# OSSI-1_EPS.net
KiCad netlist of a schematic drawn in EAGLE
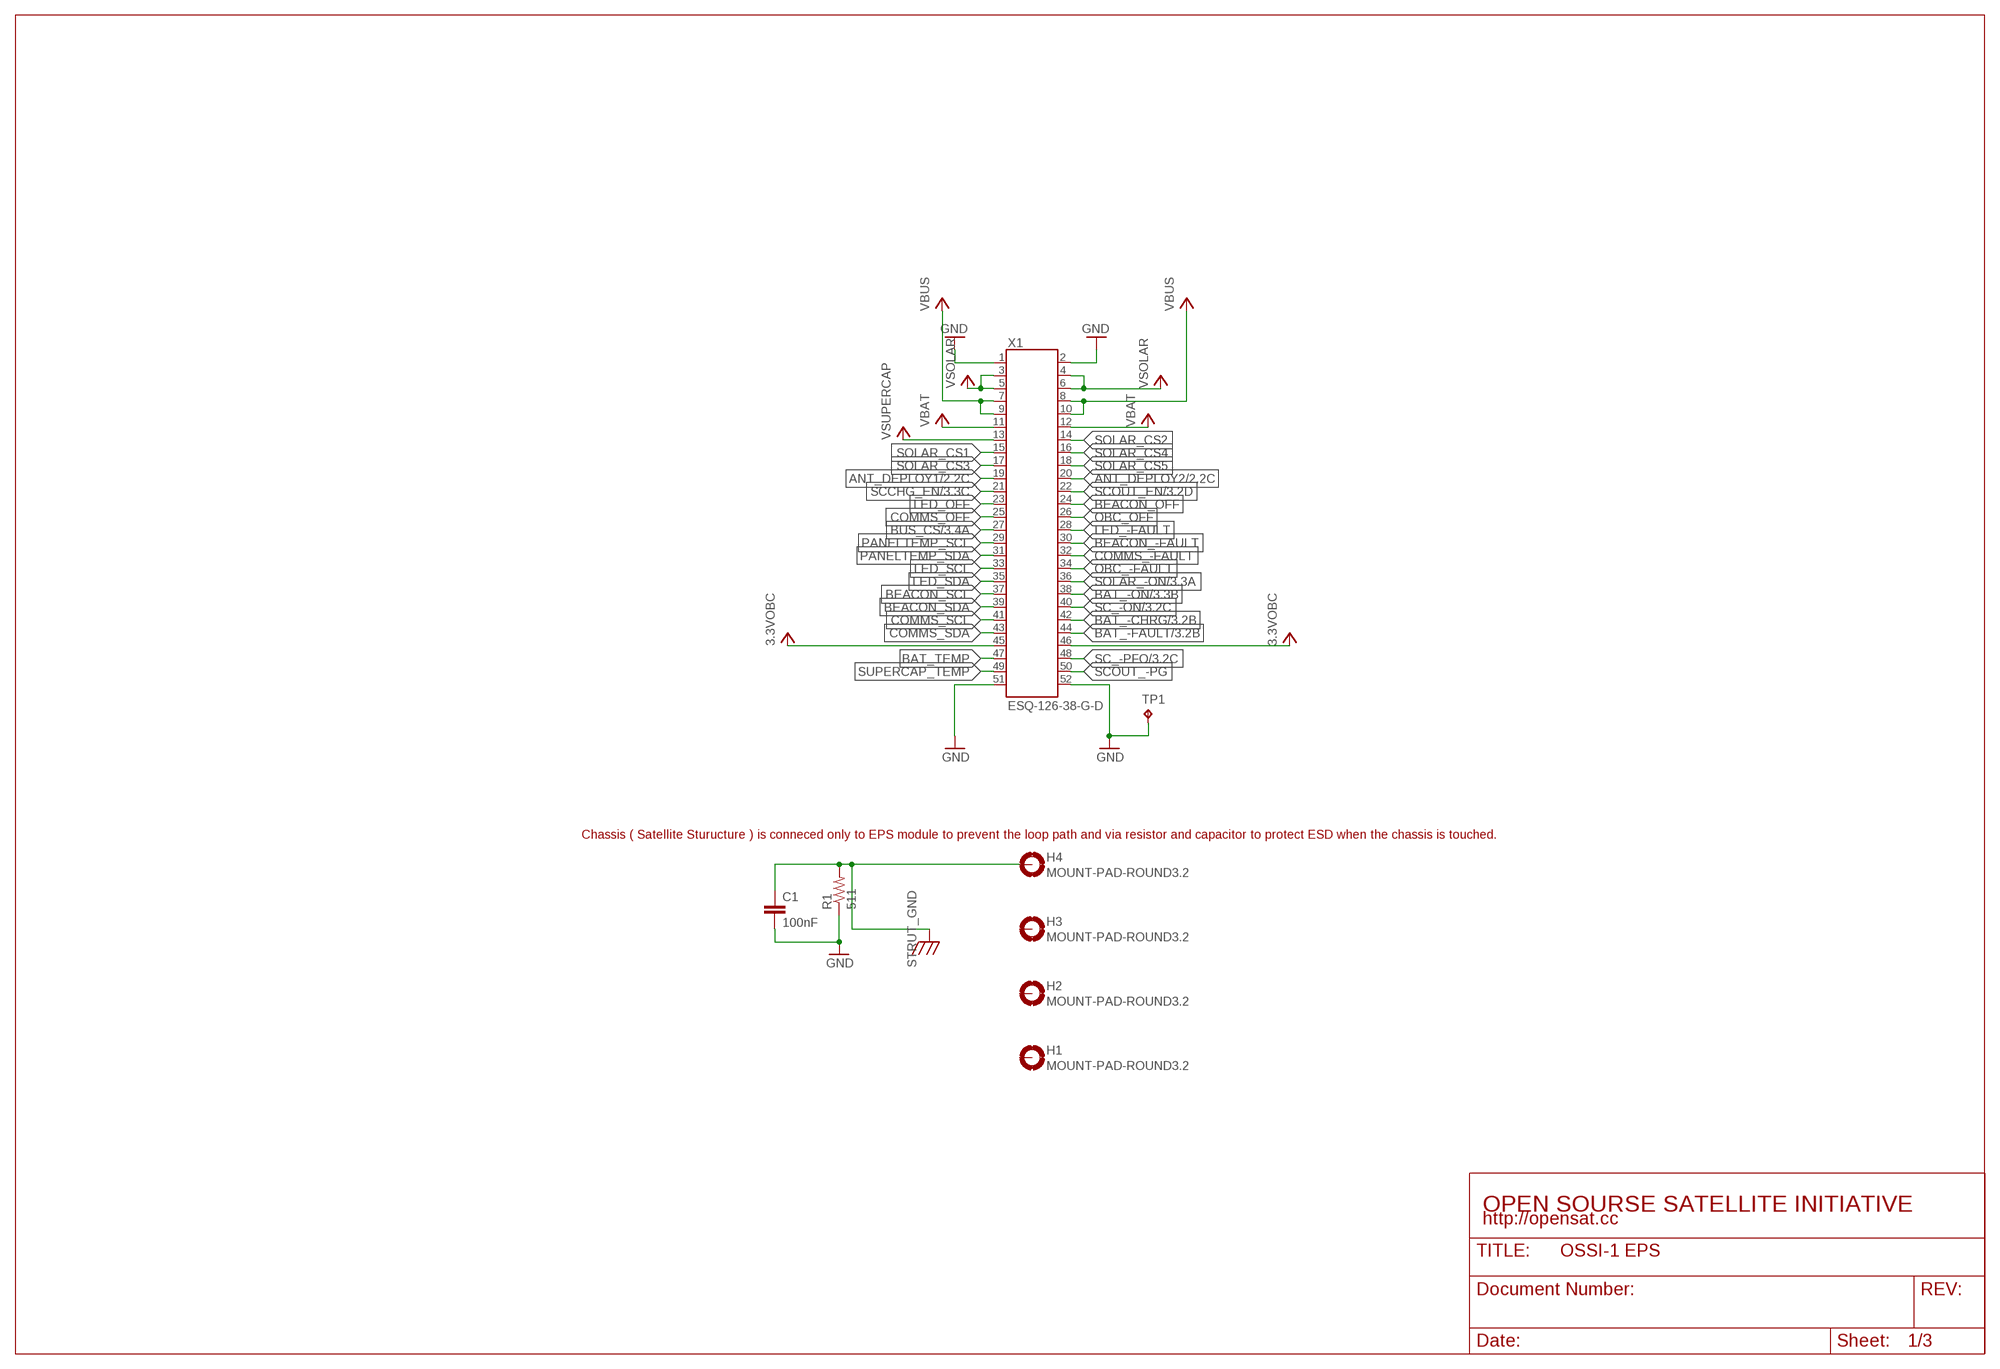
[diagram p0: schematic, sheet 1]
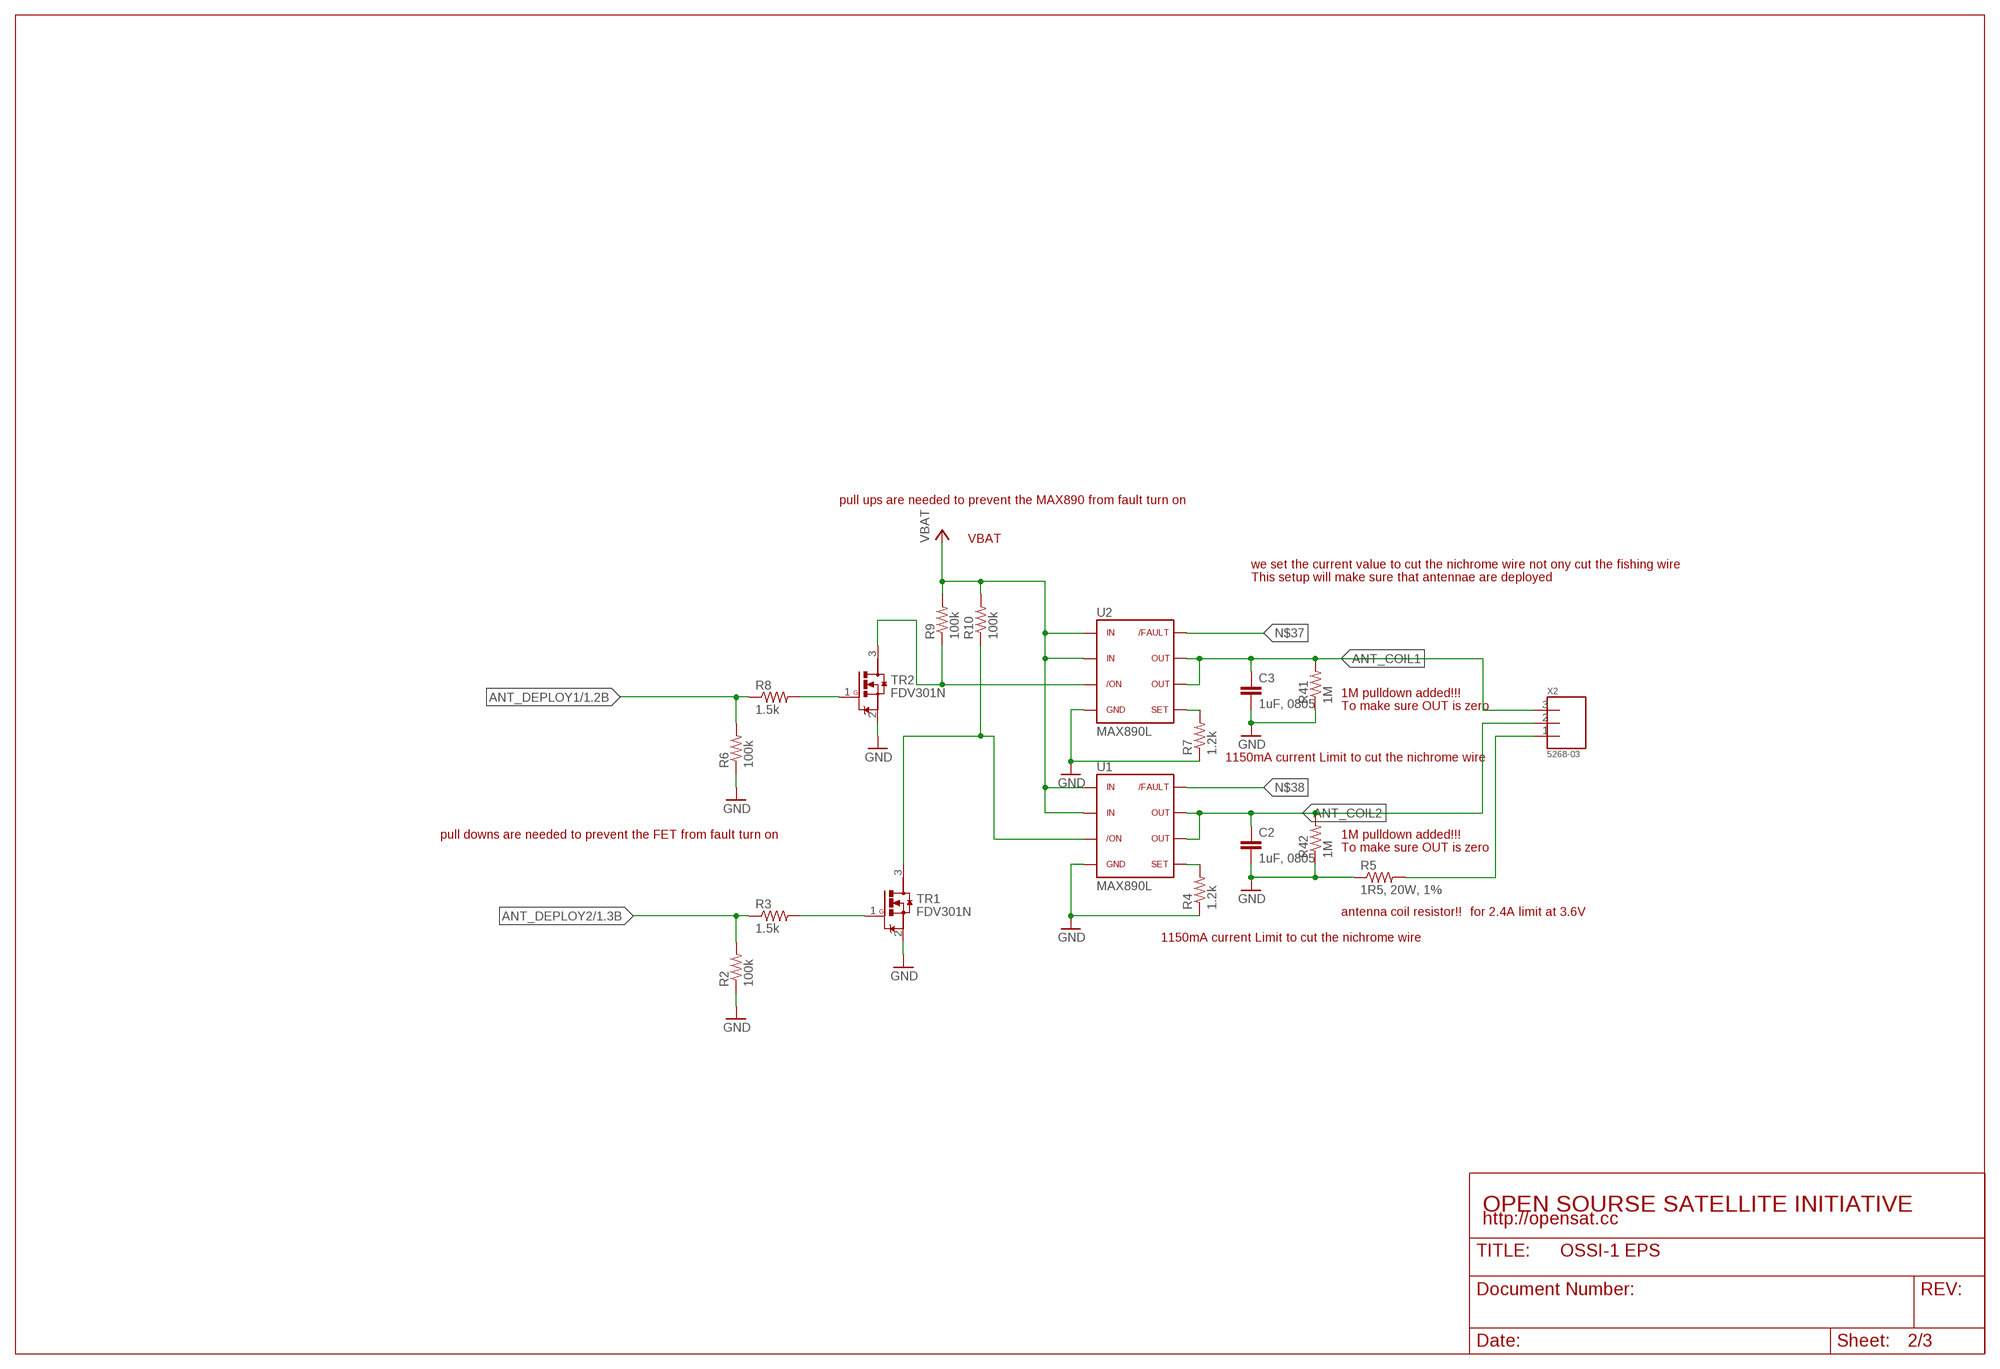
[diagram p1: schematic, sheet 2]
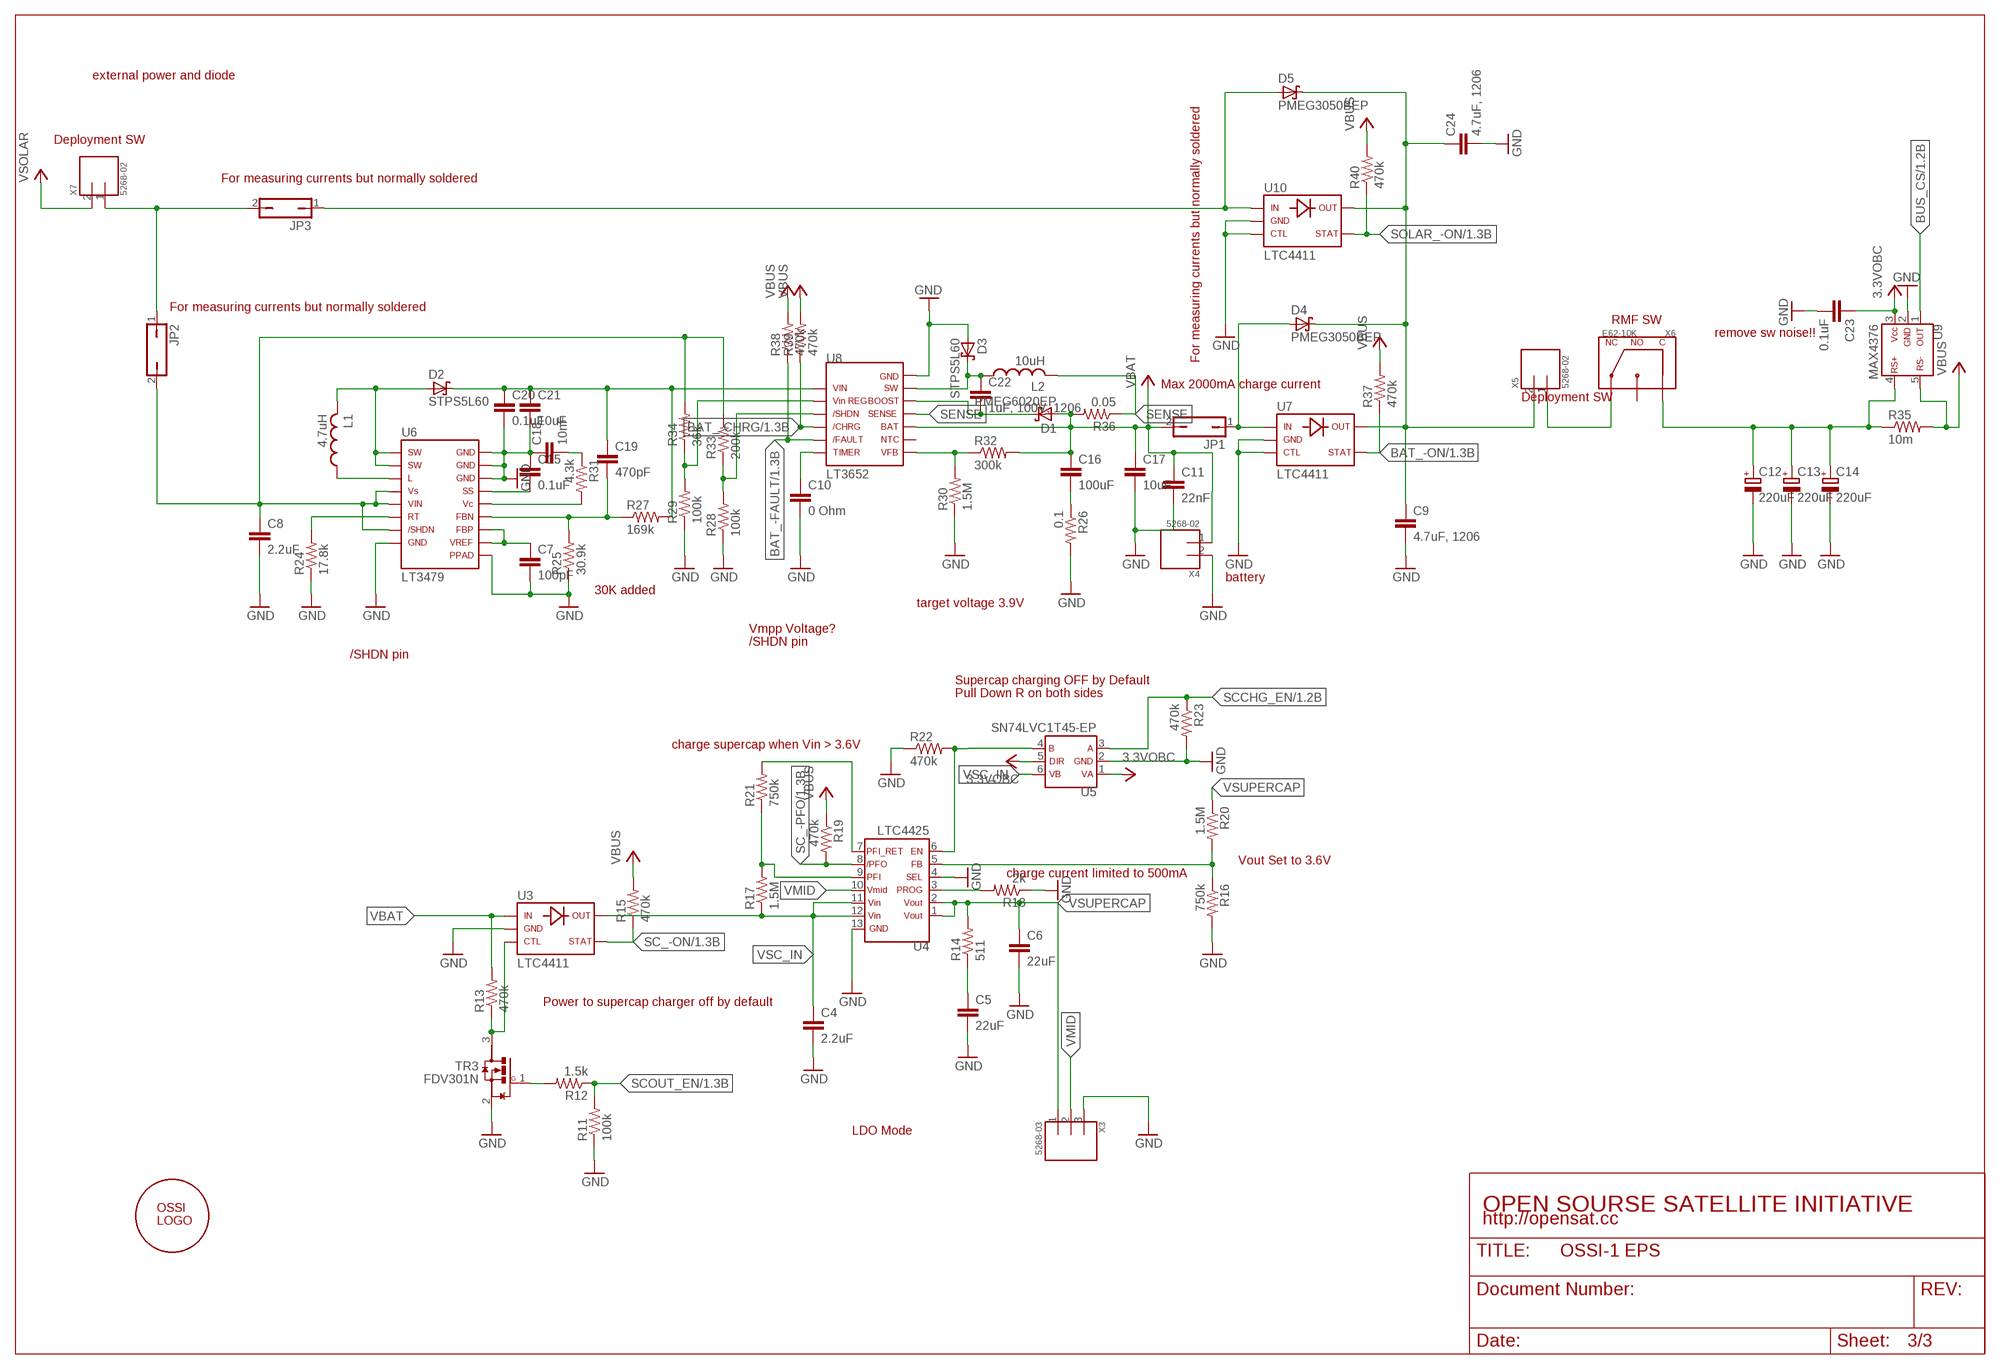
[diagram p2: schematic, sheet 3]

(export (version "E")
  (design (tool "Eeschema 10.0.6"))
  (components
    (comp (ref "C4")
      (value "2.2uF")
      (footprint "eagle-import:C1206-GCM31")
      (libsource (lib "eagle-import") (part "C1206(3216)-GCM31"))
    )
    (comp (ref "C5")
      (value "22uF")
      (footprint "eagle-import:C1210-GCM32")
      (libsource (lib "eagle-import") (part "C1210(3225)-GCM32"))
    )
    (comp (ref "C6")
      (value "22uF")
      (footprint "eagle-import:C1210-GCM32")
      (libsource (lib "eagle-import") (part "C1210(3225)-GCM32"))
    )
    (comp (ref "C7")
      (value "100pF")
      (footprint "eagle-import:C0603(1608)")
      (libsource (lib "eagle-import") (part "C0603(1608)"))
    )
    (comp (ref "C8")
      (value "2.2uF")
      (footprint "eagle-import:C1206-GCM31")
      (libsource (lib "eagle-import") (part "C1206(3216)-GCM31"))
    )
    (comp (ref "C9")
      (value "4.7uF, 1206")
      (footprint "eagle-import:C1206-GCM31")
      (libsource (lib "eagle-import") (part "C1206(3216)-GCM31"))
    )
    (comp (ref "C10")
      (value "0 Ohm")
      (footprint "eagle-import:C0603(1608)")
      (libsource (lib "eagle-import") (part "C0603(1608)"))
    )
    (comp (ref "C11")
      (value "22nF")
      (footprint "eagle-import:C0603(1608)")
      (libsource (lib "eagle-import") (part "C0603(1608)"))
    )
    (comp (ref "C12")
      (value "220uF")
      (footprint "eagle-import:C2917(7343)-Y")
      (libsource (lib "eagle-import") (part "C-TANTAL-Y"))
    )
    (comp (ref "C13")
      (value "220uF")
      (footprint "eagle-import:C2917(7343)-Y")
      (libsource (lib "eagle-import") (part "C-TANTAL-Y"))
    )
    (comp (ref "C14")
      (value "220uF")
      (footprint "eagle-import:C2917(7343)-Y")
      (libsource (lib "eagle-import") (part "C-TANTAL-Y"))
    )
    (comp (ref "C15")
      (value "0.1uF")
      (footprint "eagle-import:C0603(1608)")
      (libsource (lib "eagle-import") (part "C0603(1608)"))
    )
    (comp (ref "C16")
      (value "100uF")
      (footprint "eagle-import:C1210-TMK325")
      (libsource (lib "eagle-import") (part "C1210(3225)-TMK325"))
    )
    (comp (ref "C17")
      (value "10uF")
      (footprint "eagle-import:C1210-GCM32")
      (libsource (lib "eagle-import") (part "C1210(3225)-GCM32"))
    )
    (comp (ref "C18")
      (value "10nF")
      (footprint "eagle-import:C0603(1608)")
      (libsource (lib "eagle-import") (part "C0603(1608)"))
    )
    (comp (ref "C19")
      (value "470pF")
      (footprint "eagle-import:C0603(1608)")
      (libsource (lib "eagle-import") (part "C0603(1608)"))
    )
    (comp (ref "C20")
      (value "0.1uF")
      (footprint "eagle-import:C0603(1608)")
      (libsource (lib "eagle-import") (part "C0603(1608)"))
    )
    (comp (ref "C21")
      (value "10uF")
      (footprint "eagle-import:C1210-GCM32")
      (libsource (lib "eagle-import") (part "C1210(3225)-GCM32"))
    )
    (comp (ref "C22")
      (value "1uF, 100V, 1206")
      (footprint "eagle-import:C0805(2012)")
      (libsource (lib "eagle-import") (part "C0805(2012)"))
    )
    (comp (ref "C23")
      (value "0.1uF")
      (footprint "eagle-import:C0603(1608)")
      (libsource (lib "eagle-import") (part "C0603(1608)"))
    )
    (comp (ref "C24")
      (value "4.7uF, 1206")
      (footprint "eagle-import:C1206-GCM31")
      (libsource (lib "eagle-import") (part "C1206(3216)-GCM31"))
    )
    (comp (ref "D1")
      (value "PMEG6020EP")
      (footprint "eagle-import:PMEG6020EP")
      (libsource (lib "eagle-import") (part "PMEG6020EP"))
    )
    (comp (ref "D2")
      (value "STPS5L60")
      (footprint "eagle-import:STPS5L60")
      (libsource (lib "eagle-import") (part "STPS5L60"))
    )
    (comp (ref "D3")
      (value "STPS5L60")
      (footprint "eagle-import:STPS5L60")
      (libsource (lib "eagle-import") (part "STPS5L60"))
    )
    (comp (ref "D4")
      (value "PMEG3050BEP")
      (footprint "eagle-import:PMEG6020EP")
      (libsource (lib "eagle-import") (part "PMEG6020EP"))
    )
    (comp (ref "D5")
      (value "PMEG3050BEP")
      (footprint "eagle-import:PMEG6020EP")
      (libsource (lib "eagle-import") (part "PMEG6020EP"))
    )
    (comp (ref "JP1")
      (value "JP1Q")
      (footprint "eagle-import:JP1")
      (libsource (lib "eagle-import") (part "JP1Q"))
    )
    (comp (ref "JP2")
      (value "JP1Q")
      (footprint "eagle-import:JP1")
      (libsource (lib "eagle-import") (part "JP1Q"))
    )
    (comp (ref "JP3")
      (value "JP1Q")
      (footprint "eagle-import:JP1")
      (libsource (lib "eagle-import") (part "JP1Q"))
    )
    (comp (ref "L1")
      (value "4.7uH")
      (footprint "eagle-import:RLF7030")
      (libsource (lib "eagle-import") (part "LRLF7030"))
    )
    (comp (ref "L2")
      (value "10uH")
      (footprint "eagle-import:RLF12545")
      (libsource (lib "eagle-import") (part "LRLF12545"))
    )
    (comp (ref "R11")
      (value "100k")
      (footprint "eagle-import:R0603(1608)")
      (libsource (lib "eagle-import") (part "R0603(1608)"))
    )
    (comp (ref "R12")
      (value "1.5k")
      (footprint "eagle-import:R0603(1608)")
      (libsource (lib "eagle-import") (part "R0603(1608)"))
    )
    (comp (ref "R13")
      (value "470k")
      (footprint "eagle-import:R0603(1608)")
      (libsource (lib "eagle-import") (part "R0603(1608)"))
    )
    (comp (ref "R14")
      (value "511")
      (footprint "eagle-import:WSL1206")
      (libsource (lib "eagle-import") (part "RWSL1206"))
    )
    (comp (ref "R15")
      (value "470k")
      (footprint "eagle-import:R0603(1608)")
      (libsource (lib "eagle-import") (part "R0603(1608)"))
    )
    (comp (ref "R16")
      (value "750k")
      (footprint "eagle-import:R0603(1608)")
      (libsource (lib "eagle-import") (part "R0603(1608)"))
    )
    (comp (ref "R17")
      (value "1.5M")
      (footprint "eagle-import:R0603(1608)")
      (libsource (lib "eagle-import") (part "R0603(1608)"))
    )
    (comp (ref "R18")
      (value "2k")
      (footprint "eagle-import:R0603(1608)")
      (libsource (lib "eagle-import") (part "R0603(1608)"))
    )
    (comp (ref "R19")
      (value "470k")
      (footprint "eagle-import:R0603(1608)")
      (libsource (lib "eagle-import") (part "R0603(1608)"))
    )
    (comp (ref "R20")
      (value "1.5M")
      (footprint "eagle-import:R0603(1608)")
      (libsource (lib "eagle-import") (part "R0603(1608)"))
    )
    (comp (ref "R21")
      (value "750k")
      (footprint "eagle-import:R0603(1608)")
      (libsource (lib "eagle-import") (part "R0603(1608)"))
    )
    (comp (ref "R22")
      (value "470k")
      (footprint "eagle-import:R0603(1608)")
      (libsource (lib "eagle-import") (part "R0603(1608)"))
    )
    (comp (ref "R23")
      (value "470k")
      (footprint "eagle-import:R0603(1608)")
      (libsource (lib "eagle-import") (part "R0603(1608)"))
    )
    (comp (ref "R24")
      (value "17.8k")
      (footprint "eagle-import:R0603(1608)")
      (libsource (lib "eagle-import") (part "R0603(1608)"))
    )
    (comp (ref "R25")
      (value "30.9k")
      (footprint "eagle-import:R0603(1608)")
      (libsource (lib "eagle-import") (part "R0603(1608)"))
    )
    (comp (ref "R26")
      (value "0.1")
      (footprint "eagle-import:WSL1206")
      (libsource (lib "eagle-import") (part "RWSL1206"))
    )
    (comp (ref "R27")
      (value "169k")
      (footprint "eagle-import:R0603(1608)")
      (libsource (lib "eagle-import") (part "R0603(1608)"))
    )
    (comp (ref "R28")
      (value "100k")
      (footprint "eagle-import:R0603(1608)")
      (libsource (lib "eagle-import") (part "R0603(1608)"))
    )
    (comp (ref "R29")
      (value "100k")
      (footprint "eagle-import:R0603(1608)")
      (libsource (lib "eagle-import") (part "R0603(1608)"))
    )
    (comp (ref "R30")
      (value "1.5M")
      (footprint "eagle-import:R0603(1608)")
      (libsource (lib "eagle-import") (part "R0603(1608)"))
    )
    (comp (ref "R31")
      (value "4.3k")
      (footprint "eagle-import:R0603(1608)")
      (libsource (lib "eagle-import") (part "R0603(1608)"))
    )
    (comp (ref "R32")
      (value "300k")
      (footprint "eagle-import:R0603(1608)")
      (libsource (lib "eagle-import") (part "R0603(1608)"))
    )
    (comp (ref "R33")
      (value "200k")
      (footprint "eagle-import:R0603(1608)")
      (libsource (lib "eagle-import") (part "R0603(1608)"))
    )
    (comp (ref "R34")
      (value "36k")
      (footprint "eagle-import:R0603(1608)")
      (libsource (lib "eagle-import") (part "R0603(1608)"))
    )
    (comp (ref "R35")
      (value "10m")
      (footprint "eagle-import:WSL1206")
      (libsource (lib "eagle-import") (part "RWSL1206"))
    )
    (comp (ref "R36")
      (value "0.05")
      (footprint "eagle-import:WSL1206")
      (libsource (lib "eagle-import") (part "RWSL1206"))
    )
    (comp (ref "R37")
      (value "470k")
      (footprint "eagle-import:R0603(1608)")
      (libsource (lib "eagle-import") (part "R0603(1608)"))
    )
    (comp (ref "R38")
      (value "470k")
      (footprint "eagle-import:R0603(1608)")
      (libsource (lib "eagle-import") (part "R0603(1608)"))
    )
    (comp (ref "R39")
      (value "470k")
      (footprint "eagle-import:R0603(1608)")
      (libsource (lib "eagle-import") (part "R0603(1608)"))
    )
    (comp (ref "R40")
      (value "470k")
      (footprint "eagle-import:R0603(1608)")
      (libsource (lib "eagle-import") (part "R0603(1608)"))
    )
    (comp (ref "TR3")
      (value "FDV301N")
      (footprint "eagle-import:SOT23")
      (libsource (lib "eagle-import") (part "FDV301N"))
    )
    (comp (ref "U$1")
      (value "OSSILOGORECT")
      (footprint "eagle-import:OSSILOGORECT1005")
      (libsource (lib "eagle-import") (part "OSSILOGORECT"))
    )
    (comp (ref "U3")
      (value "LTC4411")
      (footprint "eagle-import:TSOT23-5")
      (libsource (lib "eagle-import") (part "LTC4411"))
    )
    (comp (ref "U4")
      (value "LTC4425")
      (footprint "eagle-import:MSE")
      (libsource (lib "eagle-import") (part "LTC4425"))
    )
    (comp (ref "U5")
      (value "SN74LVC1T45-EP")
      (footprint "eagle-import:SOT-6DCK")
      (libsource (lib "eagle-import") (part "SN74LVC1T45-EP"))
    )
    (comp (ref "U6")
      (value "LT3479")
      (footprint "eagle-import:TSSOP16-FE")
      (libsource (lib "eagle-import") (part "LT3479"))
    )
    (comp (ref "U7")
      (value "LTC4411")
      (footprint "eagle-import:TSOT23-5")
      (libsource (lib "eagle-import") (part "LTC4411"))
    )
    (comp (ref "U8")
      (value "LT3652")
      (footprint "eagle-import:MSE")
      (libsource (lib "eagle-import") (part "LT3652"))
    )
    (comp (ref "U9")
      (value "MAX4376")
      (footprint "eagle-import:SOT23-5DBV")
      (libsource (lib "eagle-import") (part "MAX4376"))
    )
    (comp (ref "U10")
      (value "LTC4411")
      (footprint "eagle-import:TSOT23-5")
      (libsource (lib "eagle-import") (part "LTC4411"))
    )
    (comp (ref "X3")
      (value "5268-03")
      (footprint "eagle-import:5268-03")
      (libsource (lib "eagle-import") (part "5268-03"))
    )
    (comp (ref "X4")
      (value "5268-02")
      (footprint "eagle-import:5628-02")
      (libsource (lib "eagle-import") (part "5268-02"))
    )
    (comp (ref "X5")
      (value "5268-02")
      (footprint "eagle-import:5628-02")
      (libsource (lib "eagle-import") (part "5268-02"))
    )
    (comp (ref "X6")
      (value "E62-10K")
      (footprint "eagle-import:E62-10K")
      (libsource (lib "eagle-import") (part "E62-10K"))
    )
    (comp (ref "X7")
      (value "5268-02")
      (footprint "eagle-import:5628-02")
      (libsource (lib "eagle-import") (part "5268-02"))
    )
    (comp (ref "C2")
      (value "1uF, 0805")
      (footprint "eagle-import:C0805(2012)")
      (libsource (lib "eagle-import") (part "C0805(2012)"))
    )
    (comp (ref "C3")
      (value "1uF, 0805")
      (footprint "eagle-import:C0805(2012)")
      (libsource (lib "eagle-import") (part "C0805(2012)"))
    )
    (comp (ref "R2")
      (value "100k")
      (footprint "eagle-import:R0603(1608)")
      (libsource (lib "eagle-import") (part "R0603(1608)"))
    )
    (comp (ref "R3")
      (value "1.5k")
      (footprint "eagle-import:R0603(1608)")
      (libsource (lib "eagle-import") (part "R0603(1608)"))
    )
    (comp (ref "R4")
      (value "1.2k")
      (footprint "eagle-import:R0603(1608)")
      (libsource (lib "eagle-import") (part "R0603(1608)"))
    )
    (comp (ref "R5")
      (value "1R5, 20W, 1%")
      (footprint "eagle-import:PWR263S-20")
      (libsource (lib "eagle-import") (part "RPWR263S"))
    )
    (comp (ref "R6")
      (value "100k")
      (footprint "eagle-import:R0603(1608)")
      (libsource (lib "eagle-import") (part "R0603(1608)"))
    )
    (comp (ref "R7")
      (value "1.2k")
      (footprint "eagle-import:R0603(1608)")
      (libsource (lib "eagle-import") (part "R0603(1608)"))
    )
    (comp (ref "R8")
      (value "1.5k")
      (footprint "eagle-import:R0603(1608)")
      (libsource (lib "eagle-import") (part "R0603(1608)"))
    )
    (comp (ref "R9")
      (value "100k")
      (footprint "eagle-import:R0603(1608)")
      (libsource (lib "eagle-import") (part "R0603(1608)"))
    )
    (comp (ref "R10")
      (value "100k")
      (footprint "eagle-import:R0603(1608)")
      (libsource (lib "eagle-import") (part "R0603(1608)"))
    )
    (comp (ref "R41")
      (value "1M")
      (footprint "eagle-import:R0603(1608)")
      (libsource (lib "eagle-import") (part "R0603(1608)"))
    )
    (comp (ref "R42")
      (value "1M")
      (footprint "eagle-import:R0603(1608)")
      (libsource (lib "eagle-import") (part "R0603(1608)"))
    )
    (comp (ref "TR1")
      (value "FDV301N")
      (footprint "eagle-import:SOT23")
      (libsource (lib "eagle-import") (part "FDV301N"))
    )
    (comp (ref "TR2")
      (value "FDV301N")
      (footprint "eagle-import:SOT23")
      (libsource (lib "eagle-import") (part "FDV301N"))
    )
    (comp (ref "U1")
      (value "MAX890L")
      (footprint "eagle-import:SO8")
      (libsource (lib "eagle-import") (part "MAX890L"))
    )
    (comp (ref "U2")
      (value "MAX890L")
      (footprint "eagle-import:SO8")
      (libsource (lib "eagle-import") (part "MAX890L"))
    )
    (comp (ref "X2")
      (value "5268-03")
      (footprint "eagle-import:5268-03")
      (libsource (lib "eagle-import") (part "5268-03"))
    )
    (comp (ref "C1")
      (value "100nF")
      (footprint "eagle-import:C0805(2012)")
      (libsource (lib "eagle-import") (part "C0805(2012)"))
    )
    (comp (ref "H1")
      (value "MOUNT-PAD-ROUND3.2")
      (footprint "eagle-import:3.2-PAD-ROUND")
      (libsource (lib "eagle-import") (part "MOUNT-PAD-ROUND3.2"))
    )
    (comp (ref "H2")
      (value "MOUNT-PAD-ROUND3.2")
      (footprint "eagle-import:3.2-PAD-ROUND")
      (libsource (lib "eagle-import") (part "MOUNT-PAD-ROUND3.2"))
    )
    (comp (ref "H3")
      (value "MOUNT-PAD-ROUND3.2")
      (footprint "eagle-import:3.2-PAD-ROUND")
      (libsource (lib "eagle-import") (part "MOUNT-PAD-ROUND3.2"))
    )
    (comp (ref "H4")
      (value "MOUNT-PAD-ROUND3.2")
      (footprint "eagle-import:3.2-PAD-ROUND")
      (libsource (lib "eagle-import") (part "MOUNT-PAD-ROUND3.2"))
    )
    (comp (ref "R1")
      (value "511")
      (footprint "eagle-import:WSL1206")
      (libsource (lib "eagle-import") (part "RWSL1206"))
    )
    (comp (ref "TP1")
      (value "TP")
      (footprint "eagle-import:TP-13")
      (libsource (lib "eagle-import") (part "TP"))
    )
    (comp (ref "X1")
      (value "ESQ-126-38-G-D")
      (footprint "eagle-import:ESQ-126-XX-X-D")
      (libsource (lib "eagle-import") (part "ESQ-126-38-G-D"))
    )
  )
  (nets
    (net (code "1") (name "3.3VOBC") (class "Default")
      (node (ref "C23") (pin "1") (pinfunction "1_1") (pintype "passive"))
      (node (ref "U5") (pin "1") (pinfunction "P$1_1") (pintype "bidirectional"))
      (node (ref "U5") (pin "5") (pinfunction "P$5_5") (pintype "bidirectional"))
      (node (ref "U9") (pin "3") (pinfunction "P$3_3") (pintype "power_in"))
      (node (ref "X1") (pin "45") (pinfunction "45_45") (pintype "bidirectional"))
      (node (ref "X1") (pin "46") (pinfunction "46_46") (pintype "bidirectional"))
    )
    (net (code "2") (name "ANT_COIL1") (class "Default")
      (node (ref "C3") (pin "1") (pinfunction "1_1") (pintype "passive"))
      (node (ref "R41") (pin "2") (pinfunction "2_2") (pintype "passive"))
      (node (ref "U2") (pin "6") (pinfunction "P$6_6") (pintype "output"))
      (node (ref "U2") (pin "7") (pinfunction "P$7_7") (pintype "output"))
      (node (ref "X2") (pin "3") (pinfunction "3_3") (pintype "bidirectional"))
    )
    (net (code "3") (name "ANT_COIL2") (class "Default")
      (node (ref "C2") (pin "1") (pinfunction "1_1") (pintype "passive"))
      (node (ref "R42") (pin "2") (pinfunction "2_2") (pintype "passive"))
      (node (ref "U1") (pin "6") (pinfunction "P$6_6") (pintype "output"))
      (node (ref "U1") (pin "7") (pinfunction "P$7_7") (pintype "output"))
      (node (ref "X2") (pin "2") (pinfunction "2_2") (pintype "bidirectional"))
    )
    (net (code "4") (name "ANT_DEPLOY1") (class "Default")
      (node (ref "R6") (pin "2") (pinfunction "2_2") (pintype "passive"))
      (node (ref "R8") (pin "1") (pinfunction "1_1") (pintype "passive"))
      (node (ref "X1") (pin "19") (pinfunction "19_19") (pintype "bidirectional"))
    )
    (net (code "5") (name "ANT_DEPLOY2") (class "Default")
      (node (ref "R2") (pin "2") (pinfunction "2_2") (pintype "passive"))
      (node (ref "R3") (pin "1") (pinfunction "1_1") (pintype "passive"))
      (node (ref "X1") (pin "20") (pinfunction "20_20") (pintype "bidirectional"))
    )
    (net (code "6") (name "BAT_-CHRG") (class "Default")
      (node (ref "R39") (pin "1") (pinfunction "1_1") (pintype "passive"))
      (node (ref "U8") (pin "4") (pinfunction "P$4_4") (pintype "output"))
      (node (ref "X1") (pin "42") (pinfunction "42_42") (pintype "bidirectional"))
    )
    (net (code "7") (name "BAT_-FAULT") (class "Default")
      (node (ref "R38") (pin "1") (pinfunction "1_1") (pintype "passive"))
      (node (ref "U8") (pin "5") (pinfunction "P$5_5") (pintype "output"))
      (node (ref "X1") (pin "44") (pinfunction "44_44") (pintype "bidirectional"))
    )
    (net (code "8") (name "BAT_-ON") (class "Default")
      (node (ref "R37") (pin "1") (pinfunction "1_1") (pintype "passive"))
      (node (ref "U7") (pin "P$4") (pinfunction "P$4_P$4") (pintype "output"))
      (node (ref "X1") (pin "38") (pinfunction "38_38") (pintype "bidirectional"))
    )
    (net (code "9") (name "BAT_TEMP") (class "Default")
      (node (ref "X1") (pin "47") (pinfunction "47_47") (pintype "bidirectional"))
    )
    (net (code "10") (name "BEACON_-FAULT") (class "Default")
      (node (ref "X1") (pin "30") (pinfunction "30_30") (pintype "bidirectional"))
    )
    (net (code "11") (name "BEACON_OFF") (class "Default")
      (node (ref "X1") (pin "24") (pinfunction "24_24") (pintype "bidirectional"))
    )
    (net (code "12") (name "BEACON_SCL") (class "Default")
      (node (ref "X1") (pin "37") (pinfunction "37_37") (pintype "bidirectional"))
    )
    (net (code "13") (name "BEACON_SDA") (class "Default")
      (node (ref "X1") (pin "39") (pinfunction "39_39") (pintype "bidirectional"))
    )
    (net (code "14") (name "BUS_CS") (class "Default")
      (node (ref "U9") (pin "1") (pinfunction "P$1_1") (pintype "output"))
      (node (ref "X1") (pin "27") (pinfunction "27_27") (pintype "bidirectional"))
    )
    (net (code "15") (name "COMMS_-FAULT") (class "Default")
      (node (ref "X1") (pin "32") (pinfunction "32_32") (pintype "bidirectional"))
    )
    (net (code "16") (name "COMMS_OFF") (class "Default")
      (node (ref "X1") (pin "25") (pinfunction "25_25") (pintype "bidirectional"))
    )
    (net (code "17") (name "COMMS_SCL") (class "Default")
      (node (ref "X1") (pin "41") (pinfunction "41_41") (pintype "bidirectional"))
    )
    (net (code "18") (name "COMMS_SDA") (class "Default")
      (node (ref "X1") (pin "43") (pinfunction "43_43") (pintype "bidirectional"))
    )
    (net (code "19") (name "GND") (class "Default")
      (node (ref "C1") (pin "2") (pinfunction "2_2") (pintype "passive"))
      (node (ref "C10") (pin "2") (pinfunction "2_2") (pintype "passive"))
      (node (ref "C11") (pin "2") (pinfunction "2_2") (pintype "passive"))
      (node (ref "C12") (pin "2") (pinfunction "-_2") (pintype "passive"))
      (node (ref "C13") (pin "2") (pinfunction "-_2") (pintype "passive"))
      (node (ref "C14") (pin "2") (pinfunction "-_2") (pintype "passive"))
      (node (ref "C15") (pin "1") (pinfunction "1_1") (pintype "passive"))
      (node (ref "C17") (pin "P$2") (pinfunction "2_P$2") (pintype "passive"))
      (node (ref "C18") (pin "1") (pinfunction "1_1") (pintype "passive"))
      (node (ref "C2") (pin "2") (pinfunction "2_2") (pintype "passive"))
      (node (ref "C20") (pin "2") (pinfunction "2_2") (pintype "passive"))
      (node (ref "C21") (pin "P$2") (pinfunction "2_P$2") (pintype "passive"))
      (node (ref "C23") (pin "2") (pinfunction "2_2") (pintype "passive"))
      (node (ref "C24") (pin "P$2") (pinfunction "2_P$2") (pintype "passive"))
      (node (ref "C3") (pin "2") (pinfunction "2_2") (pintype "passive"))
      (node (ref "C4") (pin "P$2") (pinfunction "2_P$2") (pintype "passive"))
      (node (ref "C5") (pin "P$2") (pinfunction "2_P$2") (pintype "passive"))
      (node (ref "C6") (pin "P$2") (pinfunction "2_P$2") (pintype "passive"))
      (node (ref "C7") (pin "2") (pinfunction "2_2") (pintype "passive"))
      (node (ref "C8") (pin "P$2") (pinfunction "2_P$2") (pintype "passive"))
      (node (ref "C9") (pin "P$2") (pinfunction "2_P$2") (pintype "passive"))
      (node (ref "D3") (pin "A") (pinfunction "A_A") (pintype "passive"))
      (node (ref "R1") (pin "P$1") (pinfunction "1_P$1") (pintype "passive"))
      (node (ref "R11") (pin "1") (pinfunction "1_1") (pintype "passive"))
      (node (ref "R16") (pin "2") (pinfunction "2_2") (pintype "passive"))
      (node (ref "R18") (pin "1") (pinfunction "1_1") (pintype "passive"))
      (node (ref "R2") (pin "1") (pinfunction "1_1") (pintype "passive"))
      (node (ref "R22") (pin "1") (pinfunction "1_1") (pintype "passive"))
      (node (ref "R23") (pin "2") (pinfunction "2_2") (pintype "passive"))
      (node (ref "R24") (pin "1") (pinfunction "1_1") (pintype "passive"))
      (node (ref "R25") (pin "1") (pinfunction "1_1") (pintype "passive"))
      (node (ref "R26") (pin "P$2") (pinfunction "2_P$2") (pintype "passive"))
      (node (ref "R28") (pin "1") (pinfunction "1_1") (pintype "passive"))
      (node (ref "R29") (pin "1") (pinfunction "1_1") (pintype "passive"))
      (node (ref "R30") (pin "1") (pinfunction "1_1") (pintype "passive"))
      (node (ref "R4") (pin "1") (pinfunction "1_1") (pintype "passive"))
      (node (ref "R41") (pin "1") (pinfunction "1_1") (pintype "passive"))
      (node (ref "R42") (pin "1") (pinfunction "1_1") (pintype "passive"))
      (node (ref "R5") (pin "P$1") (pinfunction "1_P$1") (pintype "passive"))
      (node (ref "R6") (pin "1") (pinfunction "1_1") (pintype "passive"))
      (node (ref "R7") (pin "1") (pinfunction "1_1") (pintype "passive"))
      (node (ref "TP1") (pin "TP") (pinfunction "TP_TP") (pintype "input"))
      (node (ref "TR1") (pin "2") (pinfunction "S_2") (pintype "bidirectional"))
      (node (ref "TR2") (pin "2") (pinfunction "S_2") (pintype "bidirectional"))
      (node (ref "TR3") (pin "2") (pinfunction "S_2") (pintype "bidirectional"))
      (node (ref "U1") (pin "4") (pinfunction "P$4_4") (pintype "power_in"))
      (node (ref "U10") (pin "P$2") (pinfunction "P$2_P$2") (pintype "power_in"))
      (node (ref "U10") (pin "P$3") (pinfunction "P$3_P$3") (pintype "input"))
      (node (ref "U2") (pin "4") (pinfunction "P$4_4") (pintype "power_in"))
      (node (ref "U3") (pin "P$2") (pinfunction "P$2_P$2") (pintype "power_in"))
      (node (ref "U4") (pin "13") (pinfunction "P$13_13") (pintype "power_in"))
      (node (ref "U4") (pin "4") (pinfunction "P$4_4") (pintype "input"))
      (node (ref "U5") (pin "2") (pinfunction "P$2_2") (pintype "bidirectional"))
      (node (ref "U6") (pin "14") (pinfunction "P$14_14") (pintype "power_in"))
      (node (ref "U6") (pin "15") (pinfunction "P$15_15") (pintype "power_in"))
      (node (ref "U6") (pin "16") (pinfunction "P$16_16") (pintype "power_in"))
      (node (ref "U6") (pin "8") (pinfunction "P$8_8") (pintype "power_in"))
      (node (ref "U6") (pin "PPAD") (pinfunction "P$17_PPAD") (pintype "power_in"))
      (node (ref "U7") (pin "P$2") (pinfunction "P$2_P$2") (pintype "power_in"))
      (node (ref "U7") (pin "P$3") (pinfunction "P$3_P$3") (pintype "input"))
      (node (ref "U8") (pin "13") (pinfunction "P$13_13") (pintype "bidirectional"))
      (node (ref "U9") (pin "2") (pinfunction "P$2_2") (pintype "power_in"))
      (node (ref "X1") (pin "1") (pinfunction "1_1") (pintype "bidirectional"))
      (node (ref "X1") (pin "2") (pinfunction "2_2") (pintype "bidirectional"))
      (node (ref "X1") (pin "51") (pinfunction "51_51") (pintype "bidirectional"))
      (node (ref "X1") (pin "52") (pinfunction "52_52") (pintype "bidirectional"))
      (node (ref "X3") (pin "3") (pinfunction "3_3") (pintype "bidirectional"))
      (node (ref "X4") (pin "2") (pinfunction "2_2") (pintype "bidirectional"))
    )
    (net (code "20") (name "LED_-FAULT") (class "Default")
      (node (ref "X1") (pin "28") (pinfunction "28_28") (pintype "bidirectional"))
    )
    (net (code "21") (name "LED_OFF") (class "Default")
      (node (ref "X1") (pin "23") (pinfunction "23_23") (pintype "bidirectional"))
    )
    (net (code "22") (name "LED_SCL") (class "Default")
      (node (ref "X1") (pin "33") (pinfunction "33_33") (pintype "bidirectional"))
    )
    (net (code "23") (name "LED_SDA") (class "Default")
      (node (ref "X1") (pin "35") (pinfunction "35_35") (pintype "bidirectional"))
    )
    (net (code "24") (name "N$37") (class "Default")
      (node (ref "U2") (pin "8") (pinfunction "P$8_8") (pintype "output"))
    )
    (net (code "25") (name "N$38") (class "Default")
      (node (ref "U1") (pin "8") (pinfunction "P$8_8") (pintype "output"))
    )
    (net (code "26") (name "Net-(C5-1)") (class "Default")
      (node (ref "C5") (pin "P$1") (pinfunction "1_P$1") (pintype "passive"))
      (node (ref "R14") (pin "P$1") (pinfunction "1_P$1") (pintype "passive"))
    )
    (net (code "27") (name "Net-(C8-1)") (class "Default")
      (node (ref "C8") (pin "P$1") (pinfunction "1_P$1") (pintype "passive"))
      (node (ref "JP2") (pin "2") (pinfunction "2_2") (pintype "passive"))
      (node (ref "R33") (pin "2") (pinfunction "2_2") (pintype "passive"))
      (node (ref "R34") (pin "2") (pinfunction "2_2") (pintype "passive"))
      (node (ref "U6") (pin "4") (pinfunction "P$4_4") (pintype "power_in"))
      (node (ref "U6") (pin "5") (pinfunction "P$5_5") (pintype "power_in"))
      (node (ref "U6") (pin "7") (pinfunction "P$7_7") (pintype "input"))
    )
    (net (code "28") (name "Net-(C12-+)") (class "Default")
      (node (ref "C12") (pin "1") (pinfunction "+_1") (pintype "passive"))
      (node (ref "C13") (pin "1") (pinfunction "+_1") (pintype "passive"))
      (node (ref "C14") (pin "1") (pinfunction "+_1") (pintype "passive"))
      (node (ref "R35") (pin "P$1") (pinfunction "1_P$1") (pintype "passive"))
      (node (ref "U9") (pin "4") (pinfunction "P$4_4") (pintype "input"))
      (node (ref "X6") (pin "C") (pinfunction "C_C") (pintype "bidirectional"))
    )
    (net (code "29") (name "Net-(C16-2)") (class "Default")
      (node (ref "C16") (pin "P$2") (pinfunction "2_P$2") (pintype "passive"))
      (node (ref "R26") (pin "P$1") (pinfunction "1_P$1") (pintype "passive"))
    )
    (net (code "30") (name "Net-(C18-Pad2)") (class "Default")
      (node (ref "C18") (pin "2") (pinfunction "2_2") (pintype "passive"))
      (node (ref "R31") (pin "1") (pinfunction "1_1") (pintype "passive"))
    )
    (net (code "31") (name "Net-(C21-1)") (class "Default")
      (node (ref "C19") (pin "1") (pinfunction "1_1") (pintype "passive"))
      (node (ref "C20") (pin "1") (pinfunction "1_1") (pintype "passive"))
      (node (ref "C21") (pin "P$1") (pinfunction "1_P$1") (pintype "passive"))
      (node (ref "D2") (pin "C") (pinfunction "C_C") (pintype "passive"))
      (node (ref "R27") (pin "2") (pinfunction "2_2") (pintype "passive"))
      (node (ref "U8") (pin "1") (pinfunction "P$1_1") (pintype "power_in"))
    )
    (net (code "32") (name "Net-(C24-1)") (class "Default")
      (node (ref "C24") (pin "P$1") (pinfunction "1_P$1") (pintype "passive"))
      (node (ref "C9") (pin "P$1") (pinfunction "1_P$1") (pintype "passive"))
      (node (ref "D4") (pin "C") (pinfunction "C_C") (pintype "passive"))
      (node (ref "D5") (pin "C") (pinfunction "C_C") (pintype "passive"))
      (node (ref "U10") (pin "P$5") (pinfunction "P$5_P$5") (pintype "power_in"))
      (node (ref "U7") (pin "P$5") (pinfunction "P$5_P$5") (pintype "power_in"))
      (node (ref "X5") (pin "2") (pinfunction "2_2") (pintype "bidirectional"))
    )
    (net (code "33") (name "Net-(D4-PadA)") (class "Default")
      (node (ref "D4") (pin "A") (pinfunction "A_A") (pintype "passive"))
      (node (ref "JP1") (pin "1") (pinfunction "1_1") (pintype "passive"))
      (node (ref "U7") (pin "P$1") (pinfunction "P$1_P$1") (pintype "input"))
    )
    (net (code "34") (name "Net-(D5-PadA)") (class "Default")
      (node (ref "D5") (pin "A") (pinfunction "A_A") (pintype "passive"))
      (node (ref "JP3") (pin "1") (pinfunction "1_1") (pintype "passive"))
      (node (ref "U10") (pin "P$1") (pinfunction "P$1_P$1") (pintype "input"))
    )
    (net (code "35") (name "Net-(JP2-Pad1)") (class "Default")
      (node (ref "JP2") (pin "1") (pinfunction "1_1") (pintype "passive"))
      (node (ref "JP3") (pin "2") (pinfunction "2_2") (pintype "passive"))
      (node (ref "X7") (pin "1") (pinfunction "1_1") (pintype "bidirectional"))
    )
    (net (code "36") (name "Net-(L1-1)") (class "Default")
      (node (ref "L1") (pin "P$1") (pinfunction "1_P$1") (pintype "passive"))
      (node (ref "U6") (pin "3") (pinfunction "P$3_3") (pintype "passive"))
    )
    (net (code "37") (name "Net-(L1-2)") (class "Default")
      (node (ref "D2") (pin "A") (pinfunction "A_A") (pintype "passive"))
      (node (ref "L1") (pin "P$2") (pinfunction "2_P$2") (pintype "passive"))
      (node (ref "U6") (pin "1") (pinfunction "P$1_1") (pintype "power_in"))
      (node (ref "U6") (pin "2") (pinfunction "P$2_2") (pintype "power_in"))
    )
    (net (code "38") (name "Net-(L2-1)") (class "Default")
      (node (ref "C22") (pin "1") (pinfunction "1_1") (pintype "passive"))
      (node (ref "D3") (pin "C") (pinfunction "C_C") (pintype "passive"))
      (node (ref "L2") (pin "P$1") (pinfunction "1_P$1") (pintype "passive"))
      (node (ref "U8") (pin "12") (pinfunction "P$12_12") (pintype "output"))
    )
    (net (code "39") (name "Net-(R5-2)") (class "Default")
      (node (ref "R5") (pin "P$2") (pinfunction "2_P$2") (pintype "passive"))
      (node (ref "X2") (pin "1") (pinfunction "1_1") (pintype "bidirectional"))
    )
    (net (code "40") (name "Net-(TR1-D)") (class "Default")
      (node (ref "R10") (pin "1") (pinfunction "1_1") (pintype "passive"))
      (node (ref "TR1") (pin "3") (pinfunction "D_3") (pintype "bidirectional"))
      (node (ref "U1") (pin "3") (pinfunction "P$3_3") (pintype "input"))
    )
    (net (code "41") (name "Net-(TR1-G)") (class "Default")
      (node (ref "R3") (pin "2") (pinfunction "2_2") (pintype "passive"))
      (node (ref "TR1") (pin "1") (pinfunction "G_1") (pintype "bidirectional"))
    )
    (net (code "42") (name "Net-(TR2-D)") (class "Default")
      (node (ref "R9") (pin "1") (pinfunction "1_1") (pintype "passive"))
      (node (ref "TR2") (pin "3") (pinfunction "D_3") (pintype "bidirectional"))
      (node (ref "U2") (pin "3") (pinfunction "P$3_3") (pintype "input"))
    )
    (net (code "43") (name "Net-(TR2-G)") (class "Default")
      (node (ref "R8") (pin "2") (pinfunction "2_2") (pintype "passive"))
      (node (ref "TR2") (pin "1") (pinfunction "G_1") (pintype "bidirectional"))
    )
    (net (code "44") (name "Net-(TR3-D)") (class "Default")
      (node (ref "R13") (pin "1") (pinfunction "1_1") (pintype "passive"))
      (node (ref "TR3") (pin "3") (pinfunction "D_3") (pintype "bidirectional"))
      (node (ref "U3") (pin "P$3") (pinfunction "P$3_P$3") (pintype "input"))
    )
    (net (code "45") (name "Net-(TR3-G)") (class "Default")
      (node (ref "R12") (pin "2") (pinfunction "2_2") (pintype "passive"))
      (node (ref "TR3") (pin "1") (pinfunction "G_1") (pintype "bidirectional"))
    )
    (net (code "46") (name "Net-(U1-P$5)") (class "Default")
      (node (ref "R4") (pin "2") (pinfunction "2_2") (pintype "passive"))
      (node (ref "U1") (pin "5") (pinfunction "P$5_5") (pintype "passive"))
    )
    (net (code "47") (name "Net-(U2-P$5)") (class "Default")
      (node (ref "R7") (pin "2") (pinfunction "2_2") (pintype "passive"))
      (node (ref "U2") (pin "5") (pinfunction "P$5_5") (pintype "passive"))
    )
    (net (code "48") (name "Net-(U4-P$3)") (class "Default")
      (node (ref "R18") (pin "2") (pinfunction "2_2") (pintype "passive"))
      (node (ref "U4") (pin "3") (pinfunction "P$3_3") (pintype "input"))
    )
    (net (code "49") (name "Net-(U4-P$5)") (class "Default")
      (node (ref "R16") (pin "1") (pinfunction "1_1") (pintype "passive"))
      (node (ref "R20") (pin "2") (pinfunction "2_2") (pintype "passive"))
      (node (ref "U4") (pin "5") (pinfunction "P$5_5") (pintype "input"))
    )
    (net (code "50") (name "Net-(U4-P$6)") (class "Default")
      (node (ref "R22") (pin "2") (pinfunction "2_2") (pintype "passive"))
      (node (ref "U4") (pin "6") (pinfunction "P$6_6") (pintype "input"))
      (node (ref "U5") (pin "4") (pinfunction "P$4_4") (pintype "bidirectional"))
    )
    (net (code "51") (name "Net-(U4-P$7)") (class "Default")
      (node (ref "R21") (pin "2") (pinfunction "2_2") (pintype "passive"))
      (node (ref "U4") (pin "7") (pinfunction "P$7_7") (pintype "input"))
    )
    (net (code "52") (name "Net-(U4-P$9)") (class "Default")
      (node (ref "R17") (pin "2") (pinfunction "2_2") (pintype "passive"))
      (node (ref "R21") (pin "1") (pinfunction "1_1") (pintype "passive"))
      (node (ref "U4") (pin "9") (pinfunction "P$9_9") (pintype "input"))
    )
    (net (code "53") (name "Net-(U6-P$6)") (class "Default")
      (node (ref "R24") (pin "2") (pinfunction "2_2") (pintype "passive"))
      (node (ref "U6") (pin "6") (pinfunction "P$6_6") (pintype "passive"))
    )
    (net (code "54") (name "Net-(U6-P$10)") (class "Default")
      (node (ref "C7") (pin "1") (pinfunction "1_1") (pintype "passive"))
      (node (ref "U6") (pin "10") (pinfunction "P$10_10") (pintype "input"))
      (node (ref "U6") (pin "9") (pinfunction "P$9_9") (pintype "output"))
    )
    (net (code "55") (name "Net-(U6-P$11)") (class "Default")
      (node (ref "C19") (pin "2") (pinfunction "2_2") (pintype "passive"))
      (node (ref "R25") (pin "2") (pinfunction "2_2") (pintype "passive"))
      (node (ref "R27") (pin "1") (pinfunction "1_1") (pintype "passive"))
      (node (ref "U6") (pin "11") (pinfunction "P$11_11") (pintype "input"))
    )
    (net (code "56") (name "Net-(U6-P$12)") (class "Default")
      (node (ref "R31") (pin "2") (pinfunction "2_2") (pintype "passive"))
      (node (ref "U6") (pin "12") (pinfunction "P$12_12") (pintype "input"))
    )
    (net (code "57") (name "Net-(U6-P$13)") (class "Default")
      (node (ref "C15") (pin "2") (pinfunction "2_2") (pintype "passive"))
      (node (ref "U6") (pin "13") (pinfunction "P$13_13") (pintype "input"))
    )
    (net (code "58") (name "Net-(U8-P$2)") (class "Default")
      (node (ref "R29") (pin "2") (pinfunction "2_2") (pintype "passive"))
      (node (ref "R34") (pin "1") (pinfunction "1_1") (pintype "passive"))
      (node (ref "U8") (pin "2") (pinfunction "P$2_2") (pintype "input"))
    )
    (net (code "59") (name "Net-(U8-P$3)") (class "Default")
      (node (ref "R28") (pin "2") (pinfunction "2_2") (pintype "passive"))
      (node (ref "R33") (pin "1") (pinfunction "1_1") (pintype "passive"))
      (node (ref "U8") (pin "3") (pinfunction "P$3_3") (pintype "input"))
    )
    (net (code "60") (name "Net-(U8-P$6)") (class "Default")
      (node (ref "C10") (pin "1") (pinfunction "1_1") (pintype "passive"))
      (node (ref "U8") (pin "6") (pinfunction "P$6_6") (pintype "input"))
    )
    (net (code "61") (name "Net-(U8-P$7)") (class "Default")
      (node (ref "R30") (pin "2") (pinfunction "2_2") (pintype "passive"))
      (node (ref "R32") (pin "1") (pinfunction "1_1") (pintype "passive"))
      (node (ref "U8") (pin "7") (pinfunction "P$7_7") (pintype "input"))
    )
    (net (code "62") (name "Net-(U8-P$11)") (class "Default")
      (node (ref "C22") (pin "2") (pinfunction "2_2") (pintype "passive"))
      (node (ref "D1") (pin "C") (pinfunction "C_C") (pintype "passive"))
      (node (ref "U8") (pin "11") (pinfunction "P$11_11") (pintype "input"))
    )
    (net (code "63") (name "Net-(X5-Pad1)") (class "Default")
      (node (ref "X5") (pin "1") (pinfunction "1_1") (pintype "bidirectional"))
      (node (ref "X6") (pin "NC") (pinfunction "NC_NC") (pintype "bidirectional"))
    )
    (net (code "64") (name "OBC_-FAULT") (class "Default")
      (node (ref "X1") (pin "34") (pinfunction "34_34") (pintype "bidirectional"))
    )
    (net (code "65") (name "OBC_OFF") (class "Default")
      (node (ref "X1") (pin "26") (pinfunction "26_26") (pintype "bidirectional"))
    )
    (net (code "66") (name "PANELTEMP_SCL") (class "Default")
      (node (ref "X1") (pin "29") (pinfunction "29_29") (pintype "bidirectional"))
    )
    (net (code "67") (name "PANELTEMP_SDA") (class "Default")
      (node (ref "X1") (pin "31") (pinfunction "31_31") (pintype "bidirectional"))
    )
    (net (code "68") (name "SCCHG_EN") (class "Default")
      (node (ref "R23") (pin "1") (pinfunction "1_1") (pintype "passive"))
      (node (ref "U5") (pin "3") (pinfunction "P$3_3") (pintype "bidirectional"))
      (node (ref "X1") (pin "21") (pinfunction "21_21") (pintype "bidirectional"))
    )
    (net (code "69") (name "SCOUT_-PG") (class "Default")
      (node (ref "X1") (pin "50") (pinfunction "50_50") (pintype "bidirectional"))
    )
    (net (code "70") (name "SCOUT_EN") (class "Default")
      (node (ref "R11") (pin "2") (pinfunction "2_2") (pintype "passive"))
      (node (ref "R12") (pin "1") (pinfunction "1_1") (pintype "passive"))
      (node (ref "X1") (pin "22") (pinfunction "22_22") (pintype "bidirectional"))
    )
    (net (code "71") (name "SC_-ON") (class "Default")
      (node (ref "R15") (pin "1") (pinfunction "1_1") (pintype "passive"))
      (node (ref "U3") (pin "P$4") (pinfunction "P$4_P$4") (pintype "output"))
      (node (ref "X1") (pin "40") (pinfunction "40_40") (pintype "bidirectional"))
    )
    (net (code "72") (name "SC_-PFO") (class "Default")
      (node (ref "R19") (pin "2") (pinfunction "2_2") (pintype "passive"))
      (node (ref "U4") (pin "8") (pinfunction "P$8_8") (pintype "output"))
      (node (ref "X1") (pin "48") (pinfunction "48_48") (pintype "bidirectional"))
    )
    (net (code "73") (name "SENSE") (class "Default")
      (node (ref "L2") (pin "P$2") (pinfunction "2_P$2") (pintype "passive"))
      (node (ref "R36") (pin "P$1") (pinfunction "1_P$1") (pintype "passive"))
      (node (ref "U8") (pin "10") (pinfunction "P$10_10") (pintype "input"))
    )
    (net (code "74") (name "SOLAR_-ON") (class "Default")
      (node (ref "R40") (pin "1") (pinfunction "1_1") (pintype "passive"))
      (node (ref "U10") (pin "P$4") (pinfunction "P$4_P$4") (pintype "output"))
      (node (ref "X1") (pin "36") (pinfunction "36_36") (pintype "bidirectional"))
    )
    (net (code "75") (name "SOLAR_CS1") (class "Default")
      (node (ref "X1") (pin "15") (pinfunction "15_15") (pintype "bidirectional"))
    )
    (net (code "76") (name "SOLAR_CS2") (class "Default")
      (node (ref "X1") (pin "14") (pinfunction "14_14") (pintype "bidirectional"))
    )
    (net (code "77") (name "SOLAR_CS3") (class "Default")
      (node (ref "X1") (pin "17") (pinfunction "17_17") (pintype "bidirectional"))
    )
    (net (code "78") (name "SOLAR_CS4") (class "Default")
      (node (ref "X1") (pin "16") (pinfunction "16_16") (pintype "bidirectional"))
    )
    (net (code "79") (name "SOLAR_CS5") (class "Default")
      (node (ref "X1") (pin "18") (pinfunction "18_18") (pintype "bidirectional"))
    )
    (net (code "80") (name "STRUT_GND") (class "Default")
      (node (ref "C1") (pin "1") (pinfunction "1_1") (pintype "passive"))
      (node (ref "H4") (pin "B3,2") (pinfunction "MOUNT_B3,2") (pintype "passive"))
      (node (ref "R1") (pin "P$2") (pinfunction "2_P$2") (pintype "passive"))
    )
    (net (code "81") (name "SUPERCAP_TEMP") (class "Default")
      (node (ref "X1") (pin "49") (pinfunction "49_49") (pintype "bidirectional"))
    )
    (net (code "82") (name "VBAT") (class "Default")
      (node (ref "C11") (pin "1") (pinfunction "1_1") (pintype "passive"))
      (node (ref "C16") (pin "P$1") (pinfunction "1_P$1") (pintype "passive"))
      (node (ref "C17") (pin "P$1") (pinfunction "1_P$1") (pintype "passive"))
      (node (ref "D1") (pin "A") (pinfunction "A_A") (pintype "passive"))
      (node (ref "JP1") (pin "2") (pinfunction "2_2") (pintype "passive"))
      (node (ref "R10") (pin "2") (pinfunction "2_2") (pintype "passive"))
      (node (ref "R13") (pin "2") (pinfunction "2_2") (pintype "passive"))
      (node (ref "R32") (pin "2") (pinfunction "2_2") (pintype "passive"))
      (node (ref "R36") (pin "P$2") (pinfunction "2_P$2") (pintype "passive"))
      (node (ref "R9") (pin "2") (pinfunction "2_2") (pintype "passive"))
      (node (ref "U1") (pin "1") (pinfunction "P$1_1") (pintype "input"))
      (node (ref "U1") (pin "2") (pinfunction "P$2_2") (pintype "input"))
      (node (ref "U2") (pin "1") (pinfunction "P$1_1") (pintype "input"))
      (node (ref "U2") (pin "2") (pinfunction "P$2_2") (pintype "input"))
      (node (ref "U3") (pin "P$1") (pinfunction "P$1_P$1") (pintype "input"))
      (node (ref "U8") (pin "9") (pinfunction "P$9_9") (pintype "input"))
      (node (ref "X1") (pin "11") (pinfunction "11_11") (pintype "bidirectional"))
      (node (ref "X1") (pin "12") (pinfunction "12_12") (pintype "bidirectional"))
      (node (ref "X4") (pin "1") (pinfunction "1_1") (pintype "bidirectional"))
    )
    (net (code "83") (name "VBUS") (class "Default")
      (node (ref "R15") (pin "2") (pinfunction "2_2") (pintype "passive"))
      (node (ref "R19") (pin "1") (pinfunction "1_1") (pintype "passive"))
      (node (ref "R35") (pin "P$2") (pinfunction "2_P$2") (pintype "passive"))
      (node (ref "R37") (pin "2") (pinfunction "2_2") (pintype "passive"))
      (node (ref "R38") (pin "2") (pinfunction "2_2") (pintype "passive"))
      (node (ref "R39") (pin "2") (pinfunction "2_2") (pintype "passive"))
      (node (ref "R40") (pin "2") (pinfunction "2_2") (pintype "passive"))
      (node (ref "U9") (pin "5") (pinfunction "P$5_5") (pintype "input"))
      (node (ref "X1") (pin "10") (pinfunction "10_10") (pintype "bidirectional"))
      (node (ref "X1") (pin "7") (pinfunction "7_7") (pintype "bidirectional"))
      (node (ref "X1") (pin "8") (pinfunction "8_8") (pintype "bidirectional"))
      (node (ref "X1") (pin "9") (pinfunction "9_9") (pintype "bidirectional"))
    )
    (net (code "84") (name "VMID") (class "Default")
      (node (ref "U4") (pin "10") (pinfunction "P$10_10") (pintype "power_in"))
      (node (ref "X3") (pin "2") (pinfunction "2_2") (pintype "bidirectional"))
    )
    (net (code "85") (name "VSC_IN") (class "Default")
      (node (ref "C4") (pin "P$1") (pinfunction "1_P$1") (pintype "passive"))
      (node (ref "R17") (pin "1") (pinfunction "1_1") (pintype "passive"))
      (node (ref "U3") (pin "P$5") (pinfunction "P$5_P$5") (pintype "power_in"))
      (node (ref "U4") (pin "11") (pinfunction "P$11_11") (pintype "power_in"))
      (node (ref "U4") (pin "12") (pinfunction "P$12_12") (pintype "power_in"))
      (node (ref "U5") (pin "6") (pinfunction "P$6_6") (pintype "bidirectional"))
    )
    (net (code "86") (name "VSOLAR") (class "Default")
      (node (ref "X1") (pin "3") (pinfunction "3_3") (pintype "bidirectional"))
      (node (ref "X1") (pin "4") (pinfunction "4_4") (pintype "bidirectional"))
      (node (ref "X1") (pin "5") (pinfunction "5_5") (pintype "bidirectional"))
      (node (ref "X1") (pin "6") (pinfunction "6_6") (pintype "bidirectional"))
      (node (ref "X7") (pin "2") (pinfunction "2_2") (pintype "bidirectional"))
    )
    (net (code "87") (name "VSUPERCAP") (class "Default")
      (node (ref "C6") (pin "P$1") (pinfunction "1_P$1") (pintype "passive"))
      (node (ref "R14") (pin "P$2") (pinfunction "2_P$2") (pintype "passive"))
      (node (ref "R20") (pin "1") (pinfunction "1_1") (pintype "passive"))
      (node (ref "U4") (pin "1") (pinfunction "P$1_1") (pintype "power_in"))
      (node (ref "U4") (pin "2") (pinfunction "P$2_2") (pintype "power_in"))
      (node (ref "X1") (pin "13") (pinfunction "13_13") (pintype "bidirectional"))
      (node (ref "X3") (pin "1") (pinfunction "1_1") (pintype "bidirectional"))
    )
    (net (code "88") (name "unconnected-(H1-MOUNT-PadB3,2)") (class "Default")
      (node (ref "H1") (pin "B3,2") (pinfunction "MOUNT_B3,2") (pintype "passive"))
    )
    (net (code "89") (name "unconnected-(H2-MOUNT-PadB3,2)") (class "Default")
      (node (ref "H2") (pin "B3,2") (pinfunction "MOUNT_B3,2") (pintype "passive"))
    )
    (net (code "90") (name "unconnected-(H3-MOUNT-PadB3,2)") (class "Default")
      (node (ref "H3") (pin "B3,2") (pinfunction "MOUNT_B3,2") (pintype "passive"))
    )
    (net (code "91") (name "unconnected-(U8-P$8-Pad8)") (class "Default")
      (node (ref "U8") (pin "8") (pinfunction "P$8_8") (pintype "input"))
    )
    (net (code "92") (name "unconnected-(X6-PadNO)") (class "Default")
      (node (ref "X6") (pin "NO") (pinfunction "NO_NO") (pintype "bidirectional"))
    )
  )
)
